# STM32F446RET6.net
KiCad netlist of a schematic drawn in Altium Designer
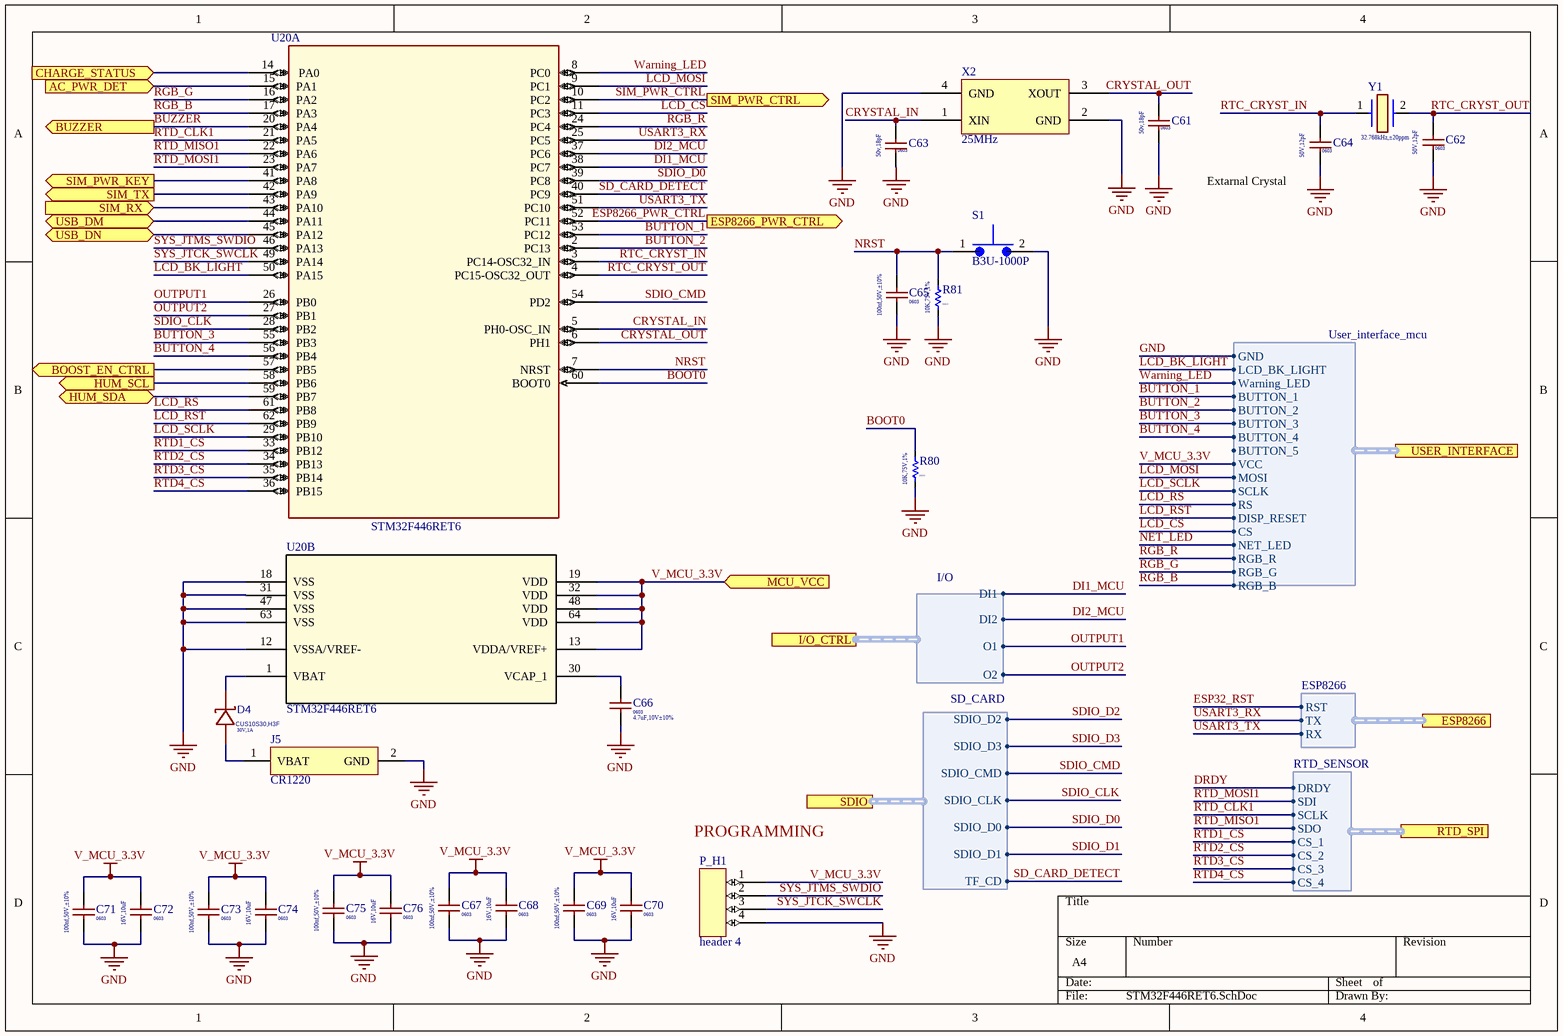
[diagram p0: STM32F446RET6.SchDoc]

(export (version "E")
  (design (tool "Eeschema 10.0.6"))
  (components
    (comp (ref "C61")
      (value "50v,18pF")
      (footprint "CAPC1608X90N")
      (description "50V 18pF NP0 ±5% 0603 Multilayer Ceramic Capacitors MLCC - SMD/SMT ROHS")
      (fields
        (field (name "MANUFACTURER") "YAGEO")
        (field (name "MPN") "CC0603JRNPO9BN180")
        (field (name "PACKAGE") "0603")
      )
      (libsource (lib "RCL") (part "CC0603JRNPO9BN180"))
    )
    (comp (ref "C62")
      (value "50V,12pF")
      (footprint "CAPC1608X90N")
      (description "50V 12pF C0G ±5% 0603 Multilayer Ceramic Capacitors MLCC - SMD/SMT ROHS")
      (fields
        (field (name "MANUFACTURER") "FH")
        (field (name "MPN") "0603CG120J500NT")
        (field (name "PACKAGE") "0603")
      )
      (libsource (lib "RCL") (part "0603CG120J500NT"))
    )
    (comp (ref "C63")
      (value "50v,18pF")
      (footprint "CAPC1608X90N")
      (description "50V 18pF NP0 ±5% 0603 Multilayer Ceramic Capacitors MLCC - SMD/SMT ROHS")
      (fields
        (field (name "MANUFACTURER") "YAGEO")
        (field (name "MPN") "CC0603JRNPO9BN180")
        (field (name "PACKAGE") "0603")
      )
      (libsource (lib "RCL") (part "CC0603JRNPO9BN180"))
    )
    (comp (ref "C64")
      (value "50V,12pF")
      (footprint "CAPC1608X90N")
      (description "50V 12pF C0G ±5% 0603 Multilayer Ceramic Capacitors MLCC - SMD/SMT ROHS")
      (fields
        (field (name "MANUFACTURER") "FH")
        (field (name "MPN") "0603CG120J500NT")
        (field (name "PACKAGE") "0603")
      )
      (libsource (lib "RCL") (part "0603CG120J500NT"))
    )
    (comp (ref "C65")
      (value "100nf,50V,±10%")
      (footprint "C0603")
      (description "50V 100nF X7R ±10% 0603 Multilayer Ceramic Capacitors MLCC - SMD/SMT ROHS")
      (fields
        (field (name "MPN") "603-CC603KRX7R9BB104")
        (field (name "MANUFACTURER") "KEMET")
        (field (name "PACKAGE") "0603")
      )
      (libsource (lib "RCL") (part "CC0603KRX7R9BB104"))
    )
    (comp (ref "C66")
      (value "4.7uF,10V±10%")
      (footprint "C0603")
      (description "10V 4.7uF X7R ±10% 0603 Multilayer Ceramic Capacitors MLCC - SMD/SMT ROHS")
      (fields
        (field (name "MPN") "CL10A475KQ8NNNC")
        (field (name "MANUFACTURER") "Samsung Electro-Mechanics")
        (field (name "PACKAGE") "0603")
      )
      (libsource (lib "RCL") (part "0603B475K100NT"))
    )
    (comp (ref "C67")
      (value "100nf,50V,±10%")
      (footprint "C0603")
      (description "50V 100nF X7R ±10% 0603 Multilayer Ceramic Capacitors MLCC - SMD/SMT ROHS")
      (fields
        (field (name "MPN") "603-CC603KRX7R9BB104")
        (field (name "MANUFACTURER") "KEMET")
        (field (name "PACKAGE") "0603")
      )
      (libsource (lib "RCL") (part "CC0603KRX7R9BB104"))
    )
    (comp (ref "C68")
      (value "16V,10uF")
      (footprint "CAPC1608X90N")
      (description "16V 10uF Y5V ±20% 0603 Multilayer Ceramic Capacitors MLCC - SMD/SMT ROHS")
      (fields
        (field (name "MANUFACTURER") "KEMET")
        (field (name "MPN") "CC0603KRX7R9BB104")
        (field (name "PACKAGE") "0603")
      )
      (libsource (lib "RCL") (part "0603F106M160NT"))
    )
    (comp (ref "C69")
      (value "100nf,50V,±10%")
      (footprint "C0603")
      (description "50V 100nF X7R ±10% 0603 Multilayer Ceramic Capacitors MLCC - SMD/SMT ROHS")
      (fields
        (field (name "MPN") "603-CC603KRX7R9BB104")
        (field (name "MANUFACTURER") "KEMET")
        (field (name "PACKAGE") "0603")
      )
      (libsource (lib "RCL") (part "CC0603KRX7R9BB104"))
    )
    (comp (ref "C70")
      (value "16V,10uF")
      (footprint "CAPC1608X90N")
      (description "16V 10uF Y5V ±20% 0603 Multilayer Ceramic Capacitors MLCC - SMD/SMT ROHS")
      (fields
        (field (name "MANUFACTURER") "KEMET")
        (field (name "MPN") "CC0603KRX7R9BB104")
        (field (name "PACKAGE") "0603")
      )
      (libsource (lib "RCL") (part "0603F106M160NT"))
    )
    (comp (ref "C71")
      (value "100nf,50V,±10%")
      (footprint "C0603")
      (description "50V 100nF X7R ±10% 0603 Multilayer Ceramic Capacitors MLCC - SMD/SMT ROHS")
      (fields
        (field (name "MPN") "603-CC603KRX7R9BB104")
        (field (name "MANUFACTURER") "KEMET")
        (field (name "PACKAGE") "0603")
      )
      (libsource (lib "RCL") (part "CC0603KRX7R9BB104"))
    )
    (comp (ref "C72")
      (value "16V,10uF")
      (footprint "CAPC1608X90N")
      (description "16V 10uF Y5V ±20% 0603 Multilayer Ceramic Capacitors MLCC - SMD/SMT ROHS")
      (fields
        (field (name "MANUFACTURER") "KEMET")
        (field (name "MPN") "CC0603KRX7R9BB104")
        (field (name "PACKAGE") "0603")
      )
      (libsource (lib "RCL") (part "0603F106M160NT"))
    )
    (comp (ref "C73")
      (value "100nf,50V,±10%")
      (footprint "C0603")
      (description "50V 100nF X7R ±10% 0603 Multilayer Ceramic Capacitors MLCC - SMD/SMT ROHS")
      (fields
        (field (name "MPN") "603-CC603KRX7R9BB104")
        (field (name "MANUFACTURER") "KEMET")
        (field (name "PACKAGE") "0603")
      )
      (libsource (lib "RCL") (part "CC0603KRX7R9BB104"))
    )
    (comp (ref "C74")
      (value "16V,10uF")
      (footprint "CAPC1608X90N")
      (description "16V 10uF Y5V ±20% 0603 Multilayer Ceramic Capacitors MLCC - SMD/SMT ROHS")
      (fields
        (field (name "MANUFACTURER") "KEMET")
        (field (name "MPN") "CC0603KRX7R9BB104")
        (field (name "PACKAGE") "0603")
      )
      (libsource (lib "RCL") (part "0603F106M160NT"))
    )
    (comp (ref "C75")
      (value "100nf,50V,±10%")
      (footprint "C0603")
      (description "50V 100nF X7R ±10% 0603 Multilayer Ceramic Capacitors MLCC - SMD/SMT ROHS")
      (fields
        (field (name "MPN") "603-CC603KRX7R9BB104")
        (field (name "MANUFACTURER") "KEMET")
        (field (name "PACKAGE") "0603")
      )
      (libsource (lib "RCL") (part "CC0603KRX7R9BB104"))
    )
    (comp (ref "C76")
      (value "16V,10uF")
      (footprint "CAPC1608X90N")
      (description "16V 10uF Y5V ±20% 0603 Multilayer Ceramic Capacitors MLCC - SMD/SMT ROHS")
      (fields
        (field (name "MANUFACTURER") "KEMET")
        (field (name "MPN") "CC0603KRX7R9BB104")
        (field (name "PACKAGE") "0603")
      )
      (libsource (lib "RCL") (part "0603F106M160NT"))
    )
    (comp (ref "D4")
      (value "CUS10S30,H3F")
      (footprint "SOD-323")
      (description "Diode 30 V 1A Schottky Barrier Diodes Surface Mount USC")
      (fields (field (name "MANUFACTURER") "TOSHIBA") (field (name "ALTIUM_VALUE") "30V,1A"))
      (libsource (lib "RCL") (part "CUS10S30,H3F"))
    )
    (comp (ref "J5")
      (value "CR1220")
      (footprint "CR1220 SMD")
      (fields (field (name "MANUFACTURER") "Q&J"))
      (libsource (lib "connector_button") (part "CR1220"))
    )
    (comp (ref "P_H1")
      (value "header 4")
      (footprint "pin header 4")
      (description "Straight 2.54mm 6mm -40℃~+105℃ 1 3mm 4 2.54mm Black Brass 1x4P Straight,P=2.54mm Pin Headers ROHS")
      (libsource (lib "connector_button") (part "header 4"))
    )
    (comp (ref "R80")
      (value "10K,75V,1%")
      (footprint "R0603")
      (description "100mW Thick Film Resistors ±100ppm/℃ ±1% 10kΩ 0603 Chip Resistor - Surface Mount ROHS")
      (fields
        (field (name "MPN") "0603WAF1002T5E")
        (field (name "MANUFACTURER") "UNI-ROYAL(Uniroyal Elec)")
        (field (name "PACKAGE") "0603")
      )
      (libsource (lib "RCL") (part "0603WAF1002T5E"))
    )
    (comp (ref "R81")
      (value "10K,75V,1%")
      (footprint "R0603")
      (description "100mW Thick Film Resistors ±100ppm/℃ ±1% 10kΩ 0603 Chip Resistor - Surface Mount ROHS")
      (fields
        (field (name "MPN") "0603WAF1002T5E")
        (field (name "MANUFACTURER") "UNI-ROYAL(Uniroyal Elec)")
        (field (name "PACKAGE") "0603")
      )
      (libsource (lib "RCL") (part "0603WAF1002T5E"))
    )
    (comp (ref "S1")
      (value "B3U-1000P")
      (footprint "B3U-1000P")
      (description "2.5mm 1.6mm Round Button 50mA Brick nogging 3mm SPST 153gf 12V SMD,2.5x3mm Tactile Switches ROHS")
      (fields (field (name "MANUFACTURER") "Omron Electronics") (field (name "MPN") "653-B3U-1000P"))
      (libsource (lib "connector_button") (part "B3U-1000P"))
    )
    (comp (ref "U20")
      (value "STM32F446RET6")
      (footprint "QFP50P1200X1200X160-64N")
      (description "IC MCU 32BIT 512KB FLASH 64LQFP")
      (fields (field (name "MANUFACTURER") "STMicroelectronics"))
      (libsource (lib "IC") (part "STM32F446RET6"))
    )
    (comp (ref "X2")
      (value "25MHz")
      (footprint "SMD Crystal")
      (description "25MHz 18pF ±10ppm ±30ppm SMD3225-4P Crystals ROHS")
      (fields (field (name "MPN") "3TJ425000XYFBC") (field (name "MANUFACTURER") "JYJE"))
      (libsource (lib "RCL") (part "3TJ425000XYFBC"))
    )
    (comp (ref "Y1")
      (value "32.768kHz,±20ppm")
      (footprint "SMD3215-2P")
      (description "32.768kHz SMD Crystal Resonator 12.5pF 70kΩ ±20ppm -40℃~+85℃ SMD3215-2P Crystals ROHS")
      (fields (field (name "MANUFACTURER") "Seiko Epson") (field (name "MPN") "Q13FC1350000400"))
      (libsource (lib "RCL") (part "Q13FC1350000400"))
    )
  )
  (nets
    (net (code "6") (name "/AC_PWR_DET") (class "Default")
      (node (ref "U20") (pin "15") (pinfunction "PA1_15") (pintype "bidirectional"))
    )
    (net (code "7") (name "/BOOST_EN_CTRL") (class "Default")
      (node (ref "U20") (pin "57") (pinfunction "PB5_57") (pintype "bidirectional"))
    )
    (net (code "8") (name "/BOOT0") (class "Default")
      (node (ref "R80") (pin "1") (pinfunction "1_1") (pintype "passive"))
      (node (ref "U20") (pin "60") (pinfunction "BOOT0_60") (pintype "input"))
    )
    (net (code "9") (name "/BUTTON_1") (class "Default")
      (node (ref "U20") (pin "53") (pinfunction "PC12_53") (pintype "bidirectional"))
    )
    (net (code "10") (name "/BUTTON_2") (class "Default")
      (node (ref "U20") (pin "2") (pinfunction "PC13_2") (pintype "bidirectional"))
    )
    (net (code "11") (name "/BUTTON_3") (class "Default")
      (node (ref "U20") (pin "55") (pinfunction "PB3_55") (pintype "bidirectional"))
    )
    (net (code "12") (name "/BUTTON_4") (class "Default")
      (node (ref "U20") (pin "56") (pinfunction "PB4_56") (pintype "bidirectional"))
    )
    (net (code "13") (name "/BUZZER") (class "Default")
      (node (ref "U20") (pin "20") (pinfunction "PA4_20") (pintype "bidirectional"))
    )
    (net (code "14") (name "/CHARGE_STATUS") (class "Default")
      (node (ref "U20") (pin "14") (pinfunction "PA0_14") (pintype "bidirectional"))
    )
    (net (code "15") (name "/CRYSTAL_IN") (class "Default")
      (node (ref "C63") (pin "2") (pinfunction "2_2") (pintype "passive"))
      (node (ref "U20") (pin "5") (pinfunction "PH0-OSC_IN_5") (pintype "bidirectional"))
      (node (ref "X2") (pin "1") (pinfunction "XIN_1") (pintype "passive"))
    )
    (net (code "16") (name "/CRYSTAL_OUT") (class "Default")
      (node (ref "C61") (pin "2") (pinfunction "2_2") (pintype "passive"))
      (node (ref "U20") (pin "6") (pinfunction "PH1_6") (pintype "bidirectional"))
      (node (ref "X2") (pin "3") (pinfunction "XOUT_3") (pintype "passive"))
    )
    (net (code "17") (name "/DI1_MCU") (class "Default")
      (node (ref "U20") (pin "38") (pinfunction "PC7_38") (pintype "bidirectional"))
    )
    (net (code "18") (name "/DI2_MCU") (class "Default")
      (node (ref "U20") (pin "37") (pinfunction "PC6_37") (pintype "bidirectional"))
    )
    (net (code "21") (name "/ESP8266_PWR_CTRL") (class "Default")
      (node (ref "U20") (pin "52") (pinfunction "PC11_52") (pintype "bidirectional"))
    )
    (net (code "22") (name "/HUM_SCL") (class "Default")
      (node (ref "U20") (pin "58") (pinfunction "PB6_58") (pintype "bidirectional"))
    )
    (net (code "23") (name "/HUM_SDA") (class "Default")
      (node (ref "U20") (pin "59") (pinfunction "PB7_59") (pintype "bidirectional"))
    )
    (net (code "24") (name "/LCD_BK_LIGHT") (class "Default")
      (node (ref "U20") (pin "50") (pinfunction "PA15_50") (pintype "bidirectional"))
    )
    (net (code "25") (name "/LCD_CS") (class "Default")
      (node (ref "U20") (pin "11") (pinfunction "PC3_11") (pintype "bidirectional"))
    )
    (net (code "26") (name "/LCD_MOSI") (class "Default")
      (node (ref "U20") (pin "9") (pinfunction "PC1_9") (pintype "bidirectional"))
    )
    (net (code "27") (name "/LCD_RS") (class "Default")
      (node (ref "U20") (pin "61") (pinfunction "PB8_61") (pintype "bidirectional"))
    )
    (net (code "28") (name "/LCD_RST") (class "Default")
      (node (ref "U20") (pin "62") (pinfunction "PB9_62") (pintype "bidirectional"))
    )
    (net (code "29") (name "/LCD_SCLK") (class "Default")
      (node (ref "U20") (pin "29") (pinfunction "PB10_29") (pintype "bidirectional"))
    )
    (net (code "31") (name "/NRST") (class "Default")
      (node (ref "C65") (pin "2") (pinfunction "2_2") (pintype "passive"))
      (node (ref "R81") (pin "1") (pinfunction "1_1") (pintype "passive"))
      (node (ref "S1") (pin "1") (pinfunction "1_1") (pintype "passive"))
      (node (ref "U20") (pin "7") (pinfunction "NRST_7") (pintype "bidirectional"))
    )
    (net (code "32") (name "/OUTPUT1") (class "Default")
      (node (ref "U20") (pin "26") (pinfunction "PB0_26") (pintype "bidirectional"))
    )
    (net (code "33") (name "/OUTPUT2") (class "Default")
      (node (ref "U20") (pin "27") (pinfunction "PB1_27") (pintype "bidirectional"))
    )
    (net (code "34") (name "/RGB_B") (class "Default")
      (node (ref "U20") (pin "17") (pinfunction "PA3_17") (pintype "bidirectional"))
    )
    (net (code "35") (name "/RGB_G") (class "Default")
      (node (ref "U20") (pin "16") (pinfunction "PA2_16") (pintype "bidirectional"))
    )
    (net (code "36") (name "/RGB_R") (class "Default")
      (node (ref "U20") (pin "24") (pinfunction "PC4_24") (pintype "bidirectional"))
    )
    (net (code "37") (name "/RTC_CRYST_IN") (class "Default")
      (node (ref "C64") (pin "2") (pinfunction "2_2") (pintype "passive"))
      (node (ref "U20") (pin "3") (pinfunction "PC14-OSC32_IN_3") (pintype "bidirectional"))
      (node (ref "Y1") (pin "1") (pinfunction "CRYSTAL_2_1") (pintype "passive"))
    )
    (net (code "38") (name "/RTC_CRYST_OUT") (class "Default")
      (node (ref "C62") (pin "2") (pinfunction "2_2") (pintype "passive"))
      (node (ref "U20") (pin "4") (pinfunction "PC15-OSC32_OUT_4") (pintype "bidirectional"))
      (node (ref "Y1") (pin "2") (pintype "passive"))
    )
    (net (code "39") (name "/RTD1_CS") (class "Default")
      (node (ref "U20") (pin "33") (pinfunction "PB12_33") (pintype "bidirectional"))
    )
    (net (code "40") (name "/RTD2_CS") (class "Default")
      (node (ref "U20") (pin "34") (pinfunction "PB13_34") (pintype "bidirectional"))
    )
    (net (code "41") (name "/RTD3_CS") (class "Default")
      (node (ref "U20") (pin "35") (pinfunction "PB14_35") (pintype "bidirectional"))
    )
    (net (code "42") (name "/RTD4_CS") (class "Default")
      (node (ref "U20") (pin "36") (pinfunction "PB15_36") (pintype "bidirectional"))
    )
    (net (code "43") (name "/RTD_CLK1") (class "Default")
      (node (ref "U20") (pin "21") (pinfunction "PA5_21") (pintype "bidirectional"))
    )
    (net (code "44") (name "/RTD_MISO1") (class "Default")
      (node (ref "U20") (pin "22") (pinfunction "PA6_22") (pintype "bidirectional"))
    )
    (net (code "45") (name "/RTD_MOSI1") (class "Default")
      (node (ref "U20") (pin "23") (pinfunction "PA7_23") (pintype "bidirectional"))
    )
    (net (code "46") (name "/SDIO_CLK") (class "Default")
      (node (ref "U20") (pin "28") (pinfunction "PB2_28") (pintype "bidirectional"))
    )
    (net (code "47") (name "/SDIO_CMD") (class "Default")
      (node (ref "U20") (pin "54") (pinfunction "PD2_54") (pintype "bidirectional"))
    )
    (net (code "48") (name "/SDIO_D0") (class "Default")
      (node (ref "U20") (pin "39") (pinfunction "PC8_39") (pintype "bidirectional"))
    )
    (net (code "52") (name "/SD_CARD_DETECT") (class "Default")
      (node (ref "U20") (pin "40") (pinfunction "PC9_40") (pintype "bidirectional"))
    )
    (net (code "53") (name "/SIM_PWR_CTRL") (class "Default")
      (node (ref "U20") (pin "10") (pinfunction "PC2_10") (pintype "bidirectional"))
    )
    (net (code "54") (name "/SIM_PWR_KEY") (class "Default")
      (node (ref "U20") (pin "41") (pinfunction "PA8_41") (pintype "bidirectional"))
    )
    (net (code "55") (name "/SIM_RX") (class "Default")
      (node (ref "U20") (pin "43") (pinfunction "PA10_43") (pintype "bidirectional"))
    )
    (net (code "56") (name "/SIM_TX") (class "Default")
      (node (ref "U20") (pin "42") (pinfunction "PA9_42") (pintype "bidirectional"))
    )
    (net (code "57") (name "/SYS_JTCK_SWCLK") (class "Default")
      (node (ref "P_H1") (pin "3") (pintype "bidirectional"))
      (node (ref "U20") (pin "49") (pinfunction "PA14_49") (pintype "bidirectional"))
    )
    (net (code "58") (name "/SYS_JTMS_SWDIO") (class "Default")
      (node (ref "P_H1") (pin "2") (pintype "bidirectional"))
      (node (ref "U20") (pin "46") (pinfunction "PA13_46") (pintype "bidirectional"))
    )
    (net (code "59") (name "/USART3_RX") (class "Default")
      (node (ref "U20") (pin "25") (pinfunction "PC5_25") (pintype "bidirectional"))
    )
    (net (code "60") (name "/USART3_TX") (class "Default")
      (node (ref "U20") (pin "51") (pinfunction "PC10_51") (pintype "bidirectional"))
    )
    (net (code "61") (name "/USB_DM") (class "Default")
      (node (ref "U20") (pin "44") (pinfunction "PA11_44") (pintype "bidirectional"))
    )
    (net (code "62") (name "/USB_DN") (class "Default")
      (node (ref "U20") (pin "45") (pinfunction "PA12_45") (pintype "bidirectional"))
    )
    (net (code "63") (name "/Warning_LED") (class "Default")
      (node (ref "U20") (pin "8") (pinfunction "PC0_8") (pintype "bidirectional"))
    )
    (net (code "69") (name "GND") (class "Default")
      (node (ref "C61") (pin "1") (pinfunction "1_1") (pintype "passive"))
      (node (ref "C62") (pin "1") (pinfunction "1_1") (pintype "passive"))
      (node (ref "C63") (pin "1") (pinfunction "1_1") (pintype "passive"))
      (node (ref "C64") (pin "1") (pinfunction "1_1") (pintype "passive"))
      (node (ref "C65") (pin "1") (pinfunction "1_1") (pintype "passive"))
      (node (ref "C66") (pin "1") (pinfunction "1_1") (pintype "passive"))
      (node (ref "C67") (pin "1") (pinfunction "1_1") (pintype "passive"))
      (node (ref "C68") (pin "1") (pinfunction "1_1") (pintype "passive"))
      (node (ref "C69") (pin "1") (pinfunction "1_1") (pintype "passive"))
      (node (ref "C70") (pin "1") (pinfunction "1_1") (pintype "passive"))
      (node (ref "C71") (pin "1") (pinfunction "1_1") (pintype "passive"))
      (node (ref "C72") (pin "1") (pinfunction "1_1") (pintype "passive"))
      (node (ref "C73") (pin "1") (pinfunction "1_1") (pintype "passive"))
      (node (ref "C74") (pin "1") (pinfunction "1_1") (pintype "passive"))
      (node (ref "C75") (pin "1") (pinfunction "1_1") (pintype "passive"))
      (node (ref "C76") (pin "1") (pinfunction "1_1") (pintype "passive"))
      (node (ref "J5") (pin "2") (pinfunction "GND_2") (pintype "passive"))
      (node (ref "P_H1") (pin "4") (pintype "bidirectional"))
      (node (ref "R80") (pin "2") (pinfunction "2_2") (pintype "passive"))
      (node (ref "R81") (pin "2") (pinfunction "2_2") (pintype "passive"))
      (node (ref "S1") (pin "2") (pinfunction "2_2") (pintype "passive"))
      (node (ref "U20") (pin "12") (pinfunction "VSSA/VREF-_12") (pintype "power_in"))
      (node (ref "U20") (pin "18") (pinfunction "VSS_18") (pintype "power_in"))
      (node (ref "U20") (pin "31") (pinfunction "VSS_31") (pintype "power_in"))
      (node (ref "U20") (pin "47") (pinfunction "VSS_47") (pintype "power_in"))
      (node (ref "U20") (pin "63") (pinfunction "VSS_63") (pintype "power_in"))
      (node (ref "X2") (pin "2") (pinfunction "GND_2") (pintype "passive"))
      (node (ref "X2") (pin "4") (pinfunction "GND_4") (pintype "passive"))
    )
    (net (code "70") (name "Net-(D4-A)") (class "Default")
      (node (ref "D4") (pin "2") (pinfunction "A_2") (pintype "passive"))
      (node (ref "J5") (pin "1") (pinfunction "VBAT_1") (pintype "passive"))
    )
    (net (code "71") (name "Net-(D4-K)") (class "Default")
      (node (ref "D4") (pin "1") (pinfunction "K_1") (pintype "passive"))
      (node (ref "U20") (pin "1") (pinfunction "VBAT_1") (pintype "power_in"))
    )
    (net (code "72") (name "Net-(U20B-VCAP_1)") (class "Default")
      (node (ref "C66") (pin "2") (pinfunction "2_2") (pintype "passive"))
      (node (ref "U20") (pin "30") (pinfunction "VCAP_1_30") (pintype "power_in"))
    )
    (net (code "73") (name "V_MCU_3.3V") (class "Default")
      (node (ref "C67") (pin "2") (pinfunction "2_2") (pintype "passive"))
      (node (ref "C68") (pin "2") (pinfunction "2_2") (pintype "passive"))
      (node (ref "C69") (pin "2") (pinfunction "2_2") (pintype "passive"))
      (node (ref "C70") (pin "2") (pinfunction "2_2") (pintype "passive"))
      (node (ref "C71") (pin "2") (pinfunction "2_2") (pintype "passive"))
      (node (ref "C72") (pin "2") (pinfunction "2_2") (pintype "passive"))
      (node (ref "C73") (pin "2") (pinfunction "2_2") (pintype "passive"))
      (node (ref "C74") (pin "2") (pinfunction "2_2") (pintype "passive"))
      (node (ref "C75") (pin "2") (pinfunction "2_2") (pintype "passive"))
      (node (ref "C76") (pin "2") (pinfunction "2_2") (pintype "passive"))
      (node (ref "P_H1") (pin "1") (pintype "bidirectional"))
      (node (ref "U20") (pin "13") (pinfunction "VDDA/VREF+_13") (pintype "power_in"))
      (node (ref "U20") (pin "19") (pinfunction "VDD_19") (pintype "power_in"))
      (node (ref "U20") (pin "32") (pinfunction "VDD_32") (pintype "power_in"))
      (node (ref "U20") (pin "48") (pinfunction "VDD_48") (pintype "power_in"))
      (node (ref "U20") (pin "64") (pinfunction "VDD_64") (pintype "power_in"))
    )
  )
)
